# soundmonsters.net
KiCad netlist of a schematic drawn in EAGLE
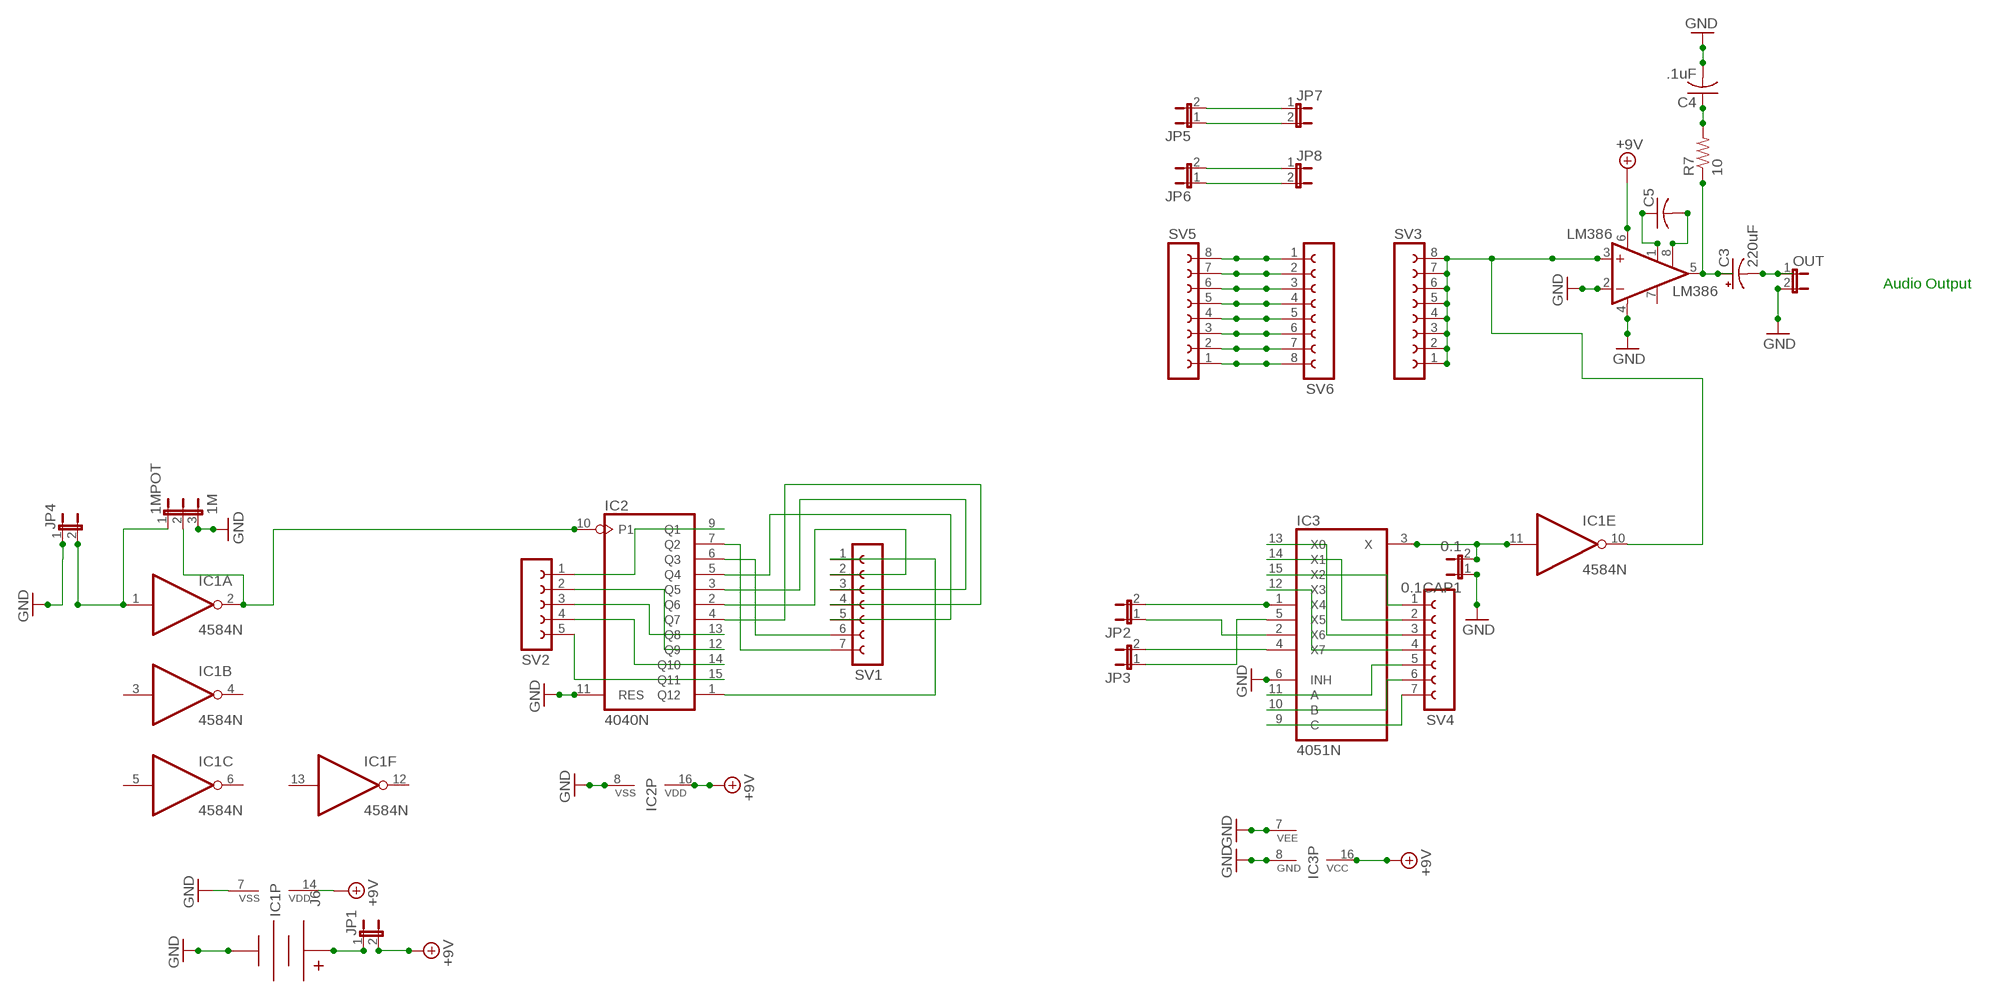
[diagram p0: schematic, sheet 1]

(export (version "E")
  (design (tool "Eeschema 10.0.6"))
  (components
    (comp (ref "0.1CAP1")
      (value "0.1")
      (footprint "eagle-import:JP1")
      (libsource (lib "eagle-import") (part "jumper_252_JP1E"))
    )
    (comp (ref "1MPOT")
      (value "1M")
      (footprint "eagle-import:JP2")
      (libsource (lib "eagle-import") (part "JP2E"))
    )
    (comp (ref "C3")
      (value "220uF")
      (footprint "eagle-import:E3,5-8")
      (libsource (lib "eagle-import") (part "CPOL-USE3.5-8"))
    )
    (comp (ref "C4")
      (value ".1uF")
      (footprint "eagle-import:C025-024X044")
      (libsource (lib "eagle-import") (part "C-US025-024X044"))
    )
    (comp (ref "C5")
      (value "C-US025-024X044")
      (footprint "eagle-import:C025-024X044")
      (libsource (lib "eagle-import") (part "C-US025-024X044"))
    )
    (comp (ref "IC1")
      (value "4584N")
      (footprint "eagle-import:DIL14")
      (libsource (lib "eagle-import") (part "4584N"))
    )
    (comp (ref "IC2")
      (value "4040N")
      (footprint "eagle-import:DIL16")
      (libsource (lib "eagle-import") (part "4040N"))
    )
    (comp (ref "IC3")
      (value "4051N")
      (footprint "eagle-import:DIL16")
      (libsource (lib "eagle-import") (part "4051N"))
    )
    (comp (ref "J6")
      (value "BC9VPC")
      (footprint "eagle-import:BC9VPC")
      (libsource (lib "eagle-import") (part "BC9VPC"))
    )
    (comp (ref "JP1")
      (value "JP1E")
      (footprint "eagle-import:JP1")
      (libsource (lib "eagle-import") (part "jumper_252_JP1E"))
    )
    (comp (ref "JP2")
      (value "JP1E")
      (footprint "eagle-import:JP1")
      (libsource (lib "eagle-import") (part "jumper_252_JP1E"))
    )
    (comp (ref "JP3")
      (value "JP1E")
      (footprint "eagle-import:JP1")
      (libsource (lib "eagle-import") (part "jumper_252_JP1E"))
    )
    (comp (ref "JP4")
      (value "JP1E")
      (footprint "eagle-import:JP1")
      (libsource (lib "eagle-import") (part "jumper_252_JP1E"))
    )
    (comp (ref "JP5")
      (value "JP1E")
      (footprint "eagle-import:JP1")
      (libsource (lib "eagle-import") (part "jumper_252_JP1E"))
    )
    (comp (ref "JP6")
      (value "JP1E")
      (footprint "eagle-import:JP1")
      (libsource (lib "eagle-import") (part "jumper_252_JP1E"))
    )
    (comp (ref "JP7")
      (value "JP1E")
      (footprint "eagle-import:JP1")
      (libsource (lib "eagle-import") (part "jumper_252_JP1E"))
    )
    (comp (ref "JP8")
      (value "JP1E")
      (footprint "eagle-import:JP1")
      (libsource (lib "eagle-import") (part "jumper_252_JP1E"))
    )
    (comp (ref "LM386")
      (value "LM386")
      (footprint "eagle-import:DIL08")
      (libsource (lib "eagle-import") (part "LM386?-N1"))
    )
    (comp (ref "OUT")
      (value "JP1E")
      (footprint "eagle-import:JP1")
      (libsource (lib "eagle-import") (part "JP1E"))
    )
    (comp (ref "R7")
      (value "10")
      (footprint "eagle-import:0204_7")
      (libsource (lib "eagle-import") (part "R-US_0204/7"))
    )
    (comp (ref "SV1")
      (value "FE07-1")
      (footprint "eagle-import:FE07")
      (libsource (lib "eagle-import") (part "FE07-1"))
    )
    (comp (ref "SV2")
      (value "FE05-1")
      (footprint "eagle-import:FE05-1")
      (libsource (lib "eagle-import") (part "FE05-1"))
    )
    (comp (ref "SV3")
      (value "FE08-1")
      (footprint "eagle-import:FE08")
      (libsource (lib "eagle-import") (part "FE08-1"))
    )
    (comp (ref "SV4")
      (value "FE07-1")
      (footprint "eagle-import:FE07")
      (libsource (lib "eagle-import") (part "FE07-1"))
    )
    (comp (ref "SV5")
      (value "FE08-1")
      (footprint "eagle-import:FE08")
      (libsource (lib "eagle-import") (part "FE08-1"))
    )
    (comp (ref "SV6")
      (value "FE08-1")
      (footprint "eagle-import:FE08")
      (libsource (lib "eagle-import") (part "FE08-1"))
    )
  )
  (nets
    (net (code "1") (name "+9V") (class "Default")
      (node (ref "IC1") (pin "14") (pinfunction "VDD_14") (pintype "power_in"))
      (node (ref "IC2") (pin "16") (pinfunction "VDD_16") (pintype "power_in"))
      (node (ref "IC3") (pin "16") (pinfunction "VCC_16") (pintype "power_in"))
      (node (ref "JP1") (pin "2") (pinfunction "2_2") (pintype "passive"))
      (node (ref "LM386") (pin "6") (pinfunction "VS_6") (pintype "power_in"))
    )
    (net (code "2") (name "GND") (class "Default")
      (node (ref "0.1CAP1") (pin "1") (pinfunction "1_1") (pintype "passive"))
      (node (ref "1MPOT") (pin "3") (pinfunction "3_3") (pintype "passive"))
      (node (ref "C4") (pin "2") (pinfunction "2_2") (pintype "passive"))
      (node (ref "IC1") (pin "7") (pinfunction "VSS_7") (pintype "power_in"))
      (node (ref "IC2") (pin "11") (pinfunction "RES_11") (pintype "input"))
      (node (ref "IC2") (pin "8") (pinfunction "VSS_8") (pintype "power_in"))
      (node (ref "IC3") (pin "6") (pinfunction "INH_6") (pintype "input"))
      (node (ref "IC3") (pin "7") (pinfunction "VEE_7") (pintype "power_in"))
      (node (ref "IC3") (pin "8") (pinfunction "GND_8") (pintype "power_in"))
      (node (ref "J6") (pin "V-") (pinfunction "V-_V-") (pintype "bidirectional"))
      (node (ref "JP4") (pin "1") (pinfunction "1_1") (pintype "passive"))
      (node (ref "LM386") (pin "2") (pinfunction "-IN_2") (pintype "input"))
      (node (ref "LM386") (pin "4") (pinfunction "GND_4") (pintype "power_in"))
      (node (ref "OUT") (pin "2") (pinfunction "2_2") (pintype "passive"))
    )
    (net (code "3") (name "Net-(C3-Pad-)") (class "Default")
      (node (ref "C3") (pin "-") (pinfunction "-_-") (pintype "passive"))
      (node (ref "OUT") (pin "1") (pinfunction "1_1") (pintype "passive"))
    )
    (net (code "4") (name "Net-(C4-Pad1)") (class "Default")
      (node (ref "C4") (pin "1") (pinfunction "1_1") (pintype "passive"))
      (node (ref "R7") (pin "2") (pinfunction "2_2") (pintype "passive"))
    )
    (net (code "5") (name "Net-(C5-Pad1)") (class "Default")
      (node (ref "C5") (pin "1") (pinfunction "1_1") (pintype "passive"))
      (node (ref "LM386") (pin "1") (pinfunction "GAIN_1") (pintype "passive"))
    )
    (net (code "6") (name "Net-(C5-Pad2)") (class "Default")
      (node (ref "C5") (pin "2") (pinfunction "2_2") (pintype "passive"))
      (node (ref "LM386") (pin "8") (pinfunction "GAIN_8") (pintype "passive"))
    )
    (net (code "7") (name "Net-(IC1A-I)") (class "Default")
      (node (ref "1MPOT") (pin "1") (pinfunction "1_1") (pintype "passive"))
      (node (ref "IC1") (pin "1") (pinfunction "I_1") (pintype "input"))
      (node (ref "JP4") (pin "2") (pinfunction "2_2") (pintype "passive"))
    )
    (net (code "8") (name "Net-(IC1A-O)") (class "Default")
      (node (ref "1MPOT") (pin "2") (pinfunction "2_2") (pintype "passive"))
      (node (ref "IC1") (pin "2") (pinfunction "O_2") (pintype "output"))
      (node (ref "IC2") (pin "10") (pinfunction "P1_10") (pintype "input"))
    )
    (net (code "9") (name "Net-(IC1E-I)") (class "Default")
      (node (ref "0.1CAP1") (pin "2") (pinfunction "2_2") (pintype "passive"))
      (node (ref "IC1") (pin "11") (pinfunction "I_11") (pintype "input"))
      (node (ref "IC3") (pin "3") (pinfunction "X_3") (pintype "bidirectional"))
    )
    (net (code "10") (name "Net-(IC1E-O)") (class "Default")
      (node (ref "IC1") (pin "10") (pinfunction "O_10") (pintype "output"))
      (node (ref "LM386") (pin "3") (pinfunction "+IN_3") (pintype "input"))
      (node (ref "SV3") (pin "1") (pinfunction "1_1") (pintype "passive"))
      (node (ref "SV3") (pin "2") (pinfunction "2_2") (pintype "passive"))
      (node (ref "SV3") (pin "3") (pinfunction "3_3") (pintype "passive"))
      (node (ref "SV3") (pin "4") (pinfunction "4_4") (pintype "passive"))
      (node (ref "SV3") (pin "5") (pinfunction "5_5") (pintype "passive"))
      (node (ref "SV3") (pin "6") (pinfunction "6_6") (pintype "passive"))
      (node (ref "SV3") (pin "7") (pinfunction "7_7") (pintype "passive"))
      (node (ref "SV3") (pin "8") (pinfunction "8_8") (pintype "passive"))
    )
    (net (code "11") (name "Net-(IC2A-Q1)") (class "Default")
      (node (ref "IC2") (pin "9") (pinfunction "Q1_9") (pintype "output"))
      (node (ref "SV2") (pin "1") (pinfunction "1_1") (pintype "passive"))
    )
    (net (code "12") (name "Net-(IC2A-Q2)") (class "Default")
      (node (ref "IC2") (pin "7") (pinfunction "Q2_7") (pintype "output"))
      (node (ref "SV1") (pin "7") (pinfunction "7_7") (pintype "passive"))
    )
    (net (code "13") (name "Net-(IC2A-Q3)") (class "Default")
      (node (ref "IC2") (pin "6") (pinfunction "Q3_6") (pintype "output"))
      (node (ref "SV1") (pin "6") (pinfunction "6_6") (pintype "passive"))
    )
    (net (code "14") (name "Net-(IC2A-Q4)") (class "Default")
      (node (ref "IC2") (pin "5") (pinfunction "Q4_5") (pintype "output"))
      (node (ref "SV1") (pin "5") (pinfunction "5_5") (pintype "passive"))
    )
    (net (code "15") (name "Net-(IC2A-Q5)") (class "Default")
      (node (ref "IC2") (pin "3") (pinfunction "Q5_3") (pintype "output"))
      (node (ref "SV1") (pin "3") (pinfunction "3_3") (pintype "passive"))
    )
    (net (code "16") (name "Net-(IC2A-Q6)") (class "Default")
      (node (ref "IC2") (pin "2") (pinfunction "Q6_2") (pintype "output"))
      (node (ref "SV1") (pin "2") (pinfunction "2_2") (pintype "passive"))
    )
    (net (code "17") (name "Net-(IC2A-Q7)") (class "Default")
      (node (ref "IC2") (pin "4") (pinfunction "Q7_4") (pintype "output"))
      (node (ref "SV1") (pin "4") (pinfunction "4_4") (pintype "passive"))
    )
    (net (code "18") (name "Net-(IC2A-Q8)") (class "Default")
      (node (ref "IC2") (pin "13") (pinfunction "Q8_13") (pintype "output"))
      (node (ref "SV2") (pin "3") (pinfunction "3_3") (pintype "passive"))
    )
    (net (code "19") (name "Net-(IC2A-Q9)") (class "Default")
      (node (ref "IC2") (pin "12") (pinfunction "Q9_12") (pintype "output"))
      (node (ref "SV2") (pin "2") (pinfunction "2_2") (pintype "passive"))
    )
    (net (code "20") (name "Net-(IC2A-Q10)") (class "Default")
      (node (ref "IC2") (pin "14") (pinfunction "Q10_14") (pintype "output"))
      (node (ref "SV2") (pin "4") (pinfunction "4_4") (pintype "passive"))
    )
    (net (code "21") (name "Net-(IC2A-Q11)") (class "Default")
      (node (ref "IC2") (pin "15") (pinfunction "Q11_15") (pintype "output"))
      (node (ref "SV2") (pin "5") (pinfunction "5_5") (pintype "passive"))
    )
    (net (code "22") (name "Net-(IC2A-Q12)") (class "Default")
      (node (ref "IC2") (pin "1") (pinfunction "Q12_1") (pintype "output"))
      (node (ref "SV1") (pin "1") (pinfunction "1_1") (pintype "passive"))
    )
    (net (code "23") (name "Net-(IC3A-A)") (class "Default")
      (node (ref "IC3") (pin "11") (pinfunction "A_11") (pintype "input"))
      (node (ref "SV4") (pin "5") (pinfunction "5_5") (pintype "passive"))
    )
    (net (code "24") (name "Net-(IC3A-B)") (class "Default")
      (node (ref "IC3") (pin "10") (pinfunction "B_10") (pintype "input"))
      (node (ref "SV4") (pin "6") (pinfunction "6_6") (pintype "passive"))
    )
    (net (code "25") (name "Net-(IC3A-C)") (class "Default")
      (node (ref "IC3") (pin "9") (pinfunction "C_9") (pintype "input"))
      (node (ref "SV4") (pin "7") (pinfunction "7_7") (pintype "passive"))
    )
    (net (code "26") (name "Net-(IC3A-X0)") (class "Default")
      (node (ref "IC3") (pin "13") (pinfunction "X0_13") (pintype "bidirectional"))
      (node (ref "SV4") (pin "3") (pinfunction "3_3") (pintype "passive"))
    )
    (net (code "27") (name "Net-(IC3A-X1)") (class "Default")
      (node (ref "IC3") (pin "14") (pinfunction "X1_14") (pintype "bidirectional"))
      (node (ref "SV4") (pin "2") (pinfunction "2_2") (pintype "passive"))
    )
    (net (code "28") (name "Net-(IC3A-X2)") (class "Default")
      (node (ref "IC3") (pin "15") (pinfunction "X2_15") (pintype "bidirectional"))
      (node (ref "SV4") (pin "1") (pinfunction "1_1") (pintype "passive"))
    )
    (net (code "29") (name "Net-(IC3A-X3)") (class "Default")
      (node (ref "IC3") (pin "12") (pinfunction "X3_12") (pintype "bidirectional"))
      (node (ref "SV4") (pin "4") (pinfunction "4_4") (pintype "passive"))
    )
    (net (code "30") (name "Net-(IC3A-X4)") (class "Default")
      (node (ref "IC3") (pin "1") (pinfunction "X4_1") (pintype "bidirectional"))
      (node (ref "JP2") (pin "2") (pinfunction "2_2") (pintype "passive"))
    )
    (net (code "31") (name "Net-(IC3A-X5)") (class "Default")
      (node (ref "IC3") (pin "5") (pinfunction "X5_5") (pintype "bidirectional"))
      (node (ref "JP3") (pin "1") (pinfunction "1_1") (pintype "passive"))
    )
    (net (code "32") (name "Net-(IC3A-X6)") (class "Default")
      (node (ref "IC3") (pin "2") (pinfunction "X6_2") (pintype "bidirectional"))
      (node (ref "JP2") (pin "1") (pinfunction "1_1") (pintype "passive"))
    )
    (net (code "33") (name "Net-(IC3A-X7)") (class "Default")
      (node (ref "IC3") (pin "4") (pinfunction "X7_4") (pintype "bidirectional"))
      (node (ref "JP3") (pin "2") (pinfunction "2_2") (pintype "passive"))
    )
    (net (code "34") (name "Net-(J6-PadV+)") (class "Default")
      (node (ref "J6") (pin "V+") (pinfunction "V+_V+") (pintype "bidirectional"))
      (node (ref "JP1") (pin "1") (pinfunction "1_1") (pintype "passive"))
    )
    (net (code "35") (name "Net-(JP5-Pad1)") (class "Default")
      (node (ref "JP5") (pin "1") (pinfunction "1_1") (pintype "passive"))
      (node (ref "JP7") (pin "2") (pinfunction "2_2") (pintype "passive"))
    )
    (net (code "36") (name "Net-(JP5-Pad2)") (class "Default")
      (node (ref "JP5") (pin "2") (pinfunction "2_2") (pintype "passive"))
      (node (ref "JP7") (pin "1") (pinfunction "1_1") (pintype "passive"))
    )
    (net (code "37") (name "Net-(JP6-Pad1)") (class "Default")
      (node (ref "JP6") (pin "1") (pinfunction "1_1") (pintype "passive"))
      (node (ref "JP8") (pin "2") (pinfunction "2_2") (pintype "passive"))
    )
    (net (code "38") (name "Net-(JP6-Pad2)") (class "Default")
      (node (ref "JP6") (pin "2") (pinfunction "2_2") (pintype "passive"))
      (node (ref "JP8") (pin "1") (pinfunction "1_1") (pintype "passive"))
    )
    (net (code "39") (name "Net-(LM386-OUT)") (class "Default")
      (node (ref "C3") (pin "+") (pinfunction "+_+") (pintype "passive"))
      (node (ref "LM386") (pin "5") (pinfunction "OUT_5") (pintype "output"))
      (node (ref "R7") (pin "1") (pinfunction "1_1") (pintype "passive"))
    )
    (net (code "40") (name "Net-(SV5-Pad1)") (class "Default")
      (node (ref "SV5") (pin "1") (pinfunction "1_1") (pintype "passive"))
      (node (ref "SV6") (pin "8") (pinfunction "8_8") (pintype "passive"))
    )
    (net (code "41") (name "Net-(SV5-Pad2)") (class "Default")
      (node (ref "SV5") (pin "2") (pinfunction "2_2") (pintype "passive"))
      (node (ref "SV6") (pin "7") (pinfunction "7_7") (pintype "passive"))
    )
    (net (code "42") (name "Net-(SV5-Pad3)") (class "Default")
      (node (ref "SV5") (pin "3") (pinfunction "3_3") (pintype "passive"))
      (node (ref "SV6") (pin "6") (pinfunction "6_6") (pintype "passive"))
    )
    (net (code "43") (name "Net-(SV5-Pad4)") (class "Default")
      (node (ref "SV5") (pin "4") (pinfunction "4_4") (pintype "passive"))
      (node (ref "SV6") (pin "5") (pinfunction "5_5") (pintype "passive"))
    )
    (net (code "44") (name "Net-(SV5-Pad5)") (class "Default")
      (node (ref "SV5") (pin "5") (pinfunction "5_5") (pintype "passive"))
      (node (ref "SV6") (pin "4") (pinfunction "4_4") (pintype "passive"))
    )
    (net (code "45") (name "Net-(SV5-Pad6)") (class "Default")
      (node (ref "SV5") (pin "6") (pinfunction "6_6") (pintype "passive"))
      (node (ref "SV6") (pin "3") (pinfunction "3_3") (pintype "passive"))
    )
    (net (code "46") (name "Net-(SV5-Pad7)") (class "Default")
      (node (ref "SV5") (pin "7") (pinfunction "7_7") (pintype "passive"))
      (node (ref "SV6") (pin "2") (pinfunction "2_2") (pintype "passive"))
    )
    (net (code "47") (name "Net-(SV5-Pad8)") (class "Default")
      (node (ref "SV5") (pin "8") (pinfunction "8_8") (pintype "passive"))
      (node (ref "SV6") (pin "1") (pinfunction "1_1") (pintype "passive"))
    )
    (net (code "48") (name "unconnected-(IC1B-I-Pad3)") (class "Default")
      (node (ref "IC1") (pin "3") (pinfunction "I_3") (pintype "input"))
    )
    (net (code "49") (name "unconnected-(IC1B-O-Pad4)") (class "Default")
      (node (ref "IC1") (pin "4") (pinfunction "O_4") (pintype "output"))
    )
    (net (code "50") (name "unconnected-(IC1C-I-Pad5)") (class "Default")
      (node (ref "IC1") (pin "5") (pinfunction "I_5") (pintype "input"))
    )
    (net (code "51") (name "unconnected-(IC1C-O-Pad6)") (class "Default")
      (node (ref "IC1") (pin "6") (pinfunction "O_6") (pintype "output"))
    )
    (net (code "52") (name "unconnected-(IC1F-I-Pad13)") (class "Default")
      (node (ref "IC1") (pin "13") (pinfunction "I_13") (pintype "input"))
    )
    (net (code "53") (name "unconnected-(IC1F-O-Pad12)") (class "Default")
      (node (ref "IC1") (pin "12") (pinfunction "O_12") (pintype "output"))
    )
    (net (code "54") (name "unconnected-(LM386-BYPASS-Pad7)") (class "Default")
      (node (ref "LM386") (pin "7") (pinfunction "BYPASS_7") (pintype "passive"))
    )
  )
)
